# Controls_PDB.net
KiCad netlist of a schematic drawn in EAGLE
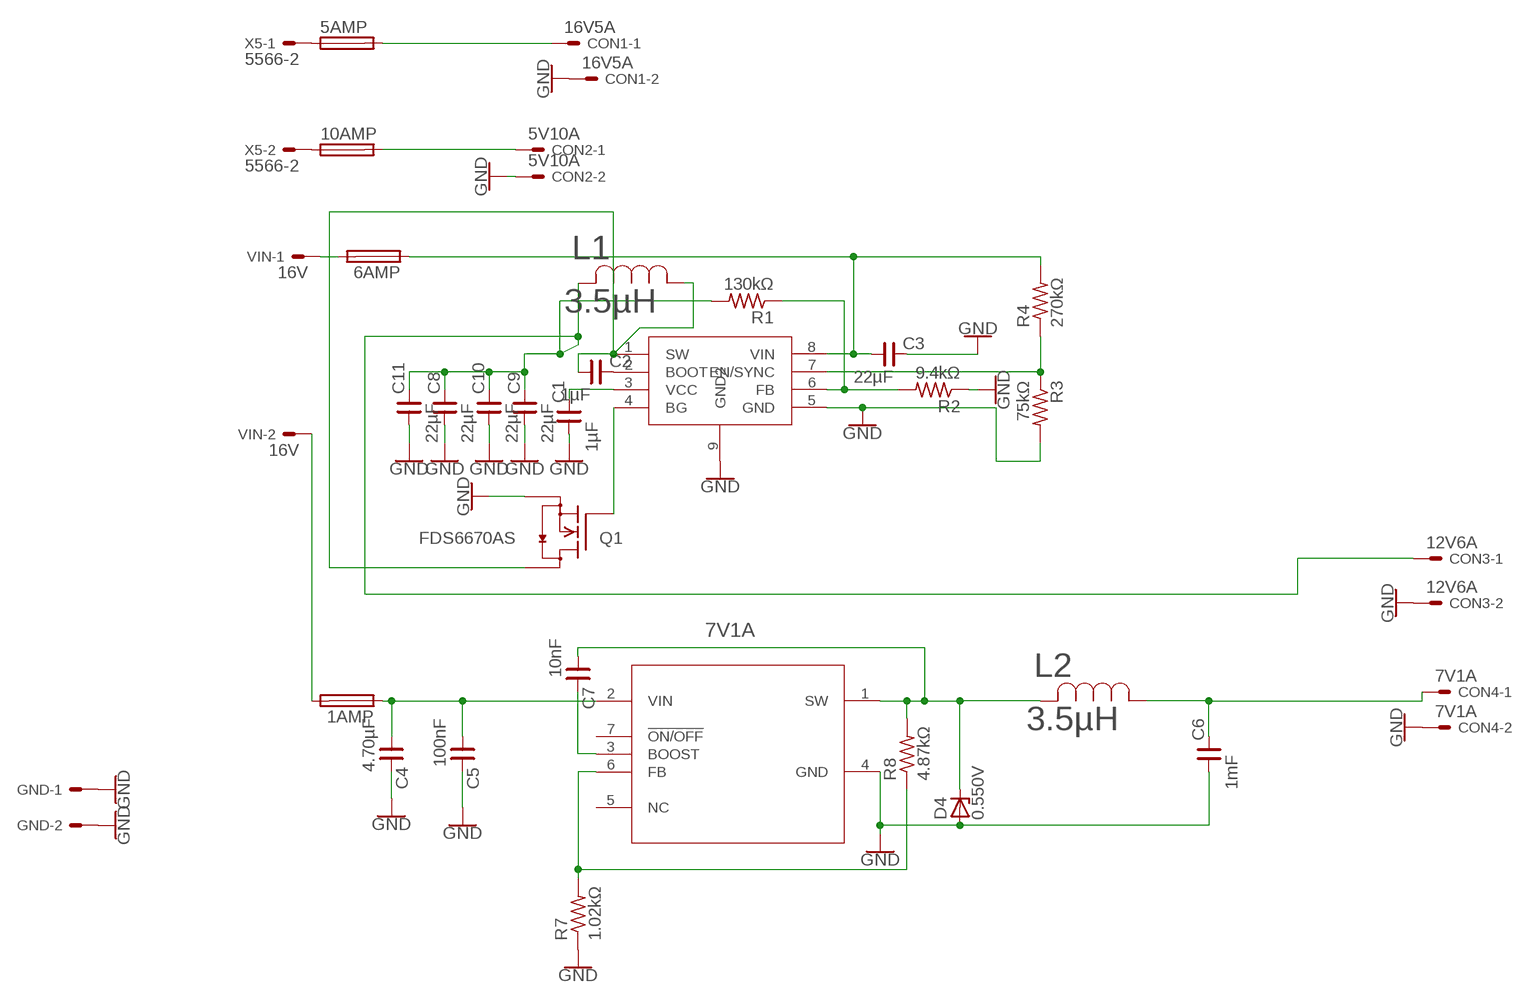
[diagram p0: schematic, sheet 1]

(export (version "E")
  (design (tool "Eeschema 10.0.6"))
  (components
    (comp (ref "1AMP")
      (value "FUSEBLANK_5X20MM")
      (footprint "eagle-import:FUSE_HOLDER_5X20MM")
      (libsource (lib "eagle-import") (part "FUSEBLANK_5X20MM"))
    )
    (comp (ref "5AMP")
      (value "FUSEBLANK_5X20MM")
      (footprint "eagle-import:FUSE_HOLDER_5X20MM")
      (libsource (lib "eagle-import") (part "FUSEBLANK_5X20MM"))
    )
    (comp (ref "6AMP")
      (value "FUSEBLANK_5X20MM")
      (footprint "eagle-import:FUSE_HOLDER_5X20MM")
      (libsource (lib "eagle-import") (part "FUSEBLANK_5X20MM"))
    )
    (comp (ref "7V1A")
      (value "LM2678T-3.3/NOPB")
      (footprint "eagle-import:TA07B")
      (fields (field (name "MANUFACTURER_PART_NUMBER") "LM2678T3.3NOPB"))
      (libsource (lib "eagle-import") (part "LM2678T-3.3/NOPB"))
    )
    (comp (ref "10AMP")
      (value "FUSEBLANK_5X20MM")
      (footprint "eagle-import:FUSE_HOLDER_5X20MM")
      (libsource (lib "eagle-import") (part "FUSEBLANK_5X20MM"))
    )
    (comp (ref "C1")
      (value "1µF")
      (footprint "eagle-import:1206")
      (libsource (lib "eagle-import") (part "CNP-1206"))
    )
    (comp (ref "C2")
      (value "1µF")
      (footprint "eagle-import:1206")
      (libsource (lib "eagle-import") (part "CNP-1206"))
    )
    (comp (ref "C3")
      (value "22µF")
      (footprint "eagle-import:1206")
      (libsource (lib "eagle-import") (part "CNP-1206"))
    )
    (comp (ref "C4")
      (value "4.70µF")
      (footprint "eagle-import:1206")
      (libsource (lib "eagle-import") (part "CNP-1206"))
    )
    (comp (ref "C5")
      (value "100nF")
      (footprint "eagle-import:1206")
      (libsource (lib "eagle-import") (part "CNP-1206"))
    )
    (comp (ref "C6")
      (value "1mF")
      (footprint "eagle-import:1206")
      (libsource (lib "eagle-import") (part "CNP-1206"))
    )
    (comp (ref "C7")
      (value "10nF")
      (footprint "eagle-import:1206")
      (libsource (lib "eagle-import") (part "CNP-1206"))
    )
    (comp (ref "C8")
      (value "22µF")
      (footprint "eagle-import:1206")
      (libsource (lib "eagle-import") (part "CNP-1206"))
    )
    (comp (ref "C9")
      (value "22µF")
      (footprint "eagle-import:1206")
      (libsource (lib "eagle-import") (part "CNP-1206"))
    )
    (comp (ref "C10")
      (value "22µF")
      (footprint "eagle-import:1206")
      (libsource (lib "eagle-import") (part "CNP-1206"))
    )
    (comp (ref "C11")
      (value "22µF")
      (footprint "eagle-import:1206")
      (libsource (lib "eagle-import") (part "CNP-1206"))
    )
    (comp (ref "CON1")
      (value "16V5A")
      (footprint "eagle-import:5566-2")
      (libsource (lib "eagle-import") (part "5566-2"))
    )
    (comp (ref "CON2")
      (value "5V10A")
      (footprint "eagle-import:5566-2")
      (libsource (lib "eagle-import") (part "5566-2"))
    )
    (comp (ref "CON3")
      (value "12V6A")
      (footprint "eagle-import:5566-2")
      (libsource (lib "eagle-import") (part "5566-2"))
    )
    (comp (ref "CON4")
      (value "7V1A")
      (footprint "eagle-import:5566-2")
      (libsource (lib "eagle-import") (part "5566-2"))
    )
    (comp (ref "D4")
      (value "0.550V")
      (footprint "eagle-import:SOD123F")
      (fields (field (name "MF") "Littelfuse") (field (name "MPN") "SMF5.0A"))
      (libsource (lib "eagle-import") (part "SMFA5.0"))
    )
    (comp (ref "GND")
      (value "5566-2")
      (footprint "eagle-import:5566-2")
      (libsource (lib "eagle-import") (part "5566-2"))
    )
    (comp (ref "L1")
      (value "3.5µH")
      (footprint "eagle-import:IND_BOURNS_SRR1260")
      (fields (field (name "MANUFACTURER_PART_NUMBER") "SRR12603R5Y"))
      (libsource (lib "eagle-import") (part "SRR1260-3R5Y"))
    )
    (comp (ref "L2")
      (value "3.5µH")
      (footprint "eagle-import:IND_BOURNS_SRR1260")
      (fields (field (name "MANUFACTURER_PART_NUMBER") "SRR12603R5Y"))
      (libsource (lib "eagle-import") (part "SRR1260-3R5Y"))
    )
    (comp (ref "Q1")
      (value "FDS6670AS")
      (footprint "eagle-import:SO-8")
      (fields (field (name "MF") "ON"))
      (libsource (lib "eagle-import") (part "FDS6670AS"))
    )
    (comp (ref "R1")
      (value "130kΩ")
      (footprint "eagle-import:R1206")
      (libsource (lib "eagle-import") (part "R-US_R1206"))
    )
    (comp (ref "R2")
      (value "9.4kΩ")
      (footprint "eagle-import:R1206")
      (libsource (lib "eagle-import") (part "R-US_R1206"))
    )
    (comp (ref "R3")
      (value "75kΩ")
      (footprint "eagle-import:R1206")
      (libsource (lib "eagle-import") (part "R-US_R1206"))
    )
    (comp (ref "R4")
      (value "270kΩ")
      (footprint "eagle-import:R1206")
      (libsource (lib "eagle-import") (part "R-US_R1206"))
    )
    (comp (ref "R7")
      (value "1.02kΩ")
      (footprint "eagle-import:R1206")
      (libsource (lib "eagle-import") (part "R-US_R1206"))
    )
    (comp (ref "R8")
      (value "4.87kΩ")
      (footprint "eagle-import:R1206")
      (libsource (lib "eagle-import") (part "R-US_R1206"))
    )
    (comp (ref "U$1")
      (value "SOIC")
      (footprint "eagle-import:SOIC127P599X175-9N")
      (libsource (lib "eagle-import") (part "SOIC"))
    )
    (comp (ref "VIN")
      (value "16V")
      (footprint "eagle-import:5566-2")
      (libsource (lib "eagle-import") (part "5566-2"))
    )
    (comp (ref "X5")
      (value "5566-2")
      (footprint "eagle-import:5566-2")
      (libsource (lib "eagle-import") (part "5566-2"))
    )
  )
  (nets
    (net (code "1") (name "GND") (class "Default")
      (node (ref "7V1A") (pin "4") (pinfunction "GND_4") (pintype "passive"))
      (node (ref "C1") (pin "P$1") (pinfunction "1_P$1") (pintype "passive"))
      (node (ref "C10") (pin "P$1") (pinfunction "1_P$1") (pintype "passive"))
      (node (ref "C11") (pin "P$1") (pinfunction "1_P$1") (pintype "passive"))
      (node (ref "C3") (pin "P$2") (pinfunction "2_P$2") (pintype "passive"))
      (node (ref "C4") (pin "P$2") (pinfunction "2_P$2") (pintype "passive"))
      (node (ref "C5") (pin "P$2") (pinfunction "2_P$2") (pintype "passive"))
      (node (ref "C6") (pin "P$1") (pinfunction "1_P$1") (pintype "passive"))
      (node (ref "C8") (pin "P$1") (pinfunction "1_P$1") (pintype "passive"))
      (node (ref "C9") (pin "P$1") (pinfunction "1_P$1") (pintype "passive"))
      (node (ref "CON1") (pin "2") (pinfunction "S_2") (pintype "passive"))
      (node (ref "CON2") (pin "2") (pinfunction "S_2") (pintype "passive"))
      (node (ref "CON3") (pin "2") (pinfunction "S_2") (pintype "passive"))
      (node (ref "CON4") (pin "2") (pinfunction "S_2") (pintype "passive"))
      (node (ref "D4") (pin "A") (pinfunction "A_A") (pintype "passive"))
      (node (ref "GND") (pin "1") (pinfunction "S_1") (pintype "passive"))
      (node (ref "GND") (pin "2") (pinfunction "S_2") (pintype "passive"))
      (node (ref "Q1") (pin "3") (pinfunction "S_3") (pintype "passive"))
      (node (ref "R2") (pin "1") (pinfunction "1_1") (pintype "passive"))
      (node (ref "R3") (pin "2") (pinfunction "2_2") (pintype "passive"))
      (node (ref "R7") (pin "1") (pinfunction "1_1") (pintype "passive"))
      (node (ref "U$1") (pin "5") (pinfunction "GND_5") (pintype "bidirectional"))
      (node (ref "U$1") (pin "9") (pinfunction "GND2_9") (pintype "bidirectional"))
    )
    (net (code "2") (name "Net-(7V1A-BOOST)") (class "Default")
      (node (ref "7V1A") (pin "3") (pinfunction "BOOST_3") (pintype "passive"))
      (node (ref "C7") (pin "P$2") (pinfunction "2_P$2") (pintype "passive"))
    )
    (net (code "3") (name "Net-(7V1A-FB)") (class "Default")
      (node (ref "7V1A") (pin "6") (pinfunction "FB_6") (pintype "passive"))
      (node (ref "R7") (pin "2") (pinfunction "2_2") (pintype "passive"))
      (node (ref "R8") (pin "1") (pinfunction "1_1") (pintype "passive"))
    )
    (net (code "4") (name "Net-(7V1A-SW)") (class "Default")
      (node (ref "7V1A") (pin "1") (pinfunction "SW_1") (pintype "output"))
      (node (ref "C7") (pin "P$1") (pinfunction "1_P$1") (pintype "passive"))
      (node (ref "D4") (pin "C") (pinfunction "C_C") (pintype "passive"))
      (node (ref "L2") (pin "2") (pinfunction "2_2") (pintype "passive"))
      (node (ref "R8") (pin "2") (pinfunction "2_2") (pintype "passive"))
    )
    (net (code "5") (name "Net-(7V1A-VIN)") (class "Default")
      (node (ref "1AMP") (pin "1") (pinfunction "1_1") (pintype "passive"))
      (node (ref "7V1A") (pin "2") (pinfunction "VIN_2") (pintype "input"))
      (node (ref "C4") (pin "P$1") (pinfunction "1_P$1") (pintype "passive"))
      (node (ref "C5") (pin "P$1") (pinfunction "1_P$1") (pintype "passive"))
    )
    (net (code "6") (name "Net-(C1-2)") (class "Default")
      (node (ref "C1") (pin "P$2") (pinfunction "2_P$2") (pintype "passive"))
      (node (ref "U$1") (pin "3") (pinfunction "VCC_3") (pintype "bidirectional"))
    )
    (net (code "7") (name "Net-(C2-1)") (class "Default")
      (node (ref "C2") (pin "P$1") (pinfunction "1_P$1") (pintype "passive"))
      (node (ref "L1") (pin "1") (pinfunction "1_1") (pintype "passive"))
      (node (ref "Q1") (pin "8") (pinfunction "D_8") (pintype "passive"))
      (node (ref "U$1") (pin "1") (pinfunction "SW_1") (pintype "bidirectional"))
    )
    (net (code "8") (name "Net-(C2-2)") (class "Default")
      (node (ref "C2") (pin "P$2") (pinfunction "2_P$2") (pintype "passive"))
      (node (ref "U$1") (pin "2") (pinfunction "BOOT_2") (pintype "bidirectional"))
    )
    (net (code "9") (name "Net-(C3-1)") (class "Default")
      (node (ref "6AMP") (pin "1") (pinfunction "1_1") (pintype "passive"))
      (node (ref "C3") (pin "P$1") (pinfunction "1_P$1") (pintype "passive"))
      (node (ref "R4") (pin "2") (pinfunction "2_2") (pintype "passive"))
      (node (ref "U$1") (pin "8") (pinfunction "VIN_8") (pintype "bidirectional"))
    )
    (net (code "10") (name "Net-(C6-2)") (class "Default")
      (node (ref "C6") (pin "P$2") (pinfunction "2_P$2") (pintype "passive"))
      (node (ref "CON4") (pin "1") (pinfunction "S_1") (pintype "passive"))
      (node (ref "L2") (pin "1") (pinfunction "1_1") (pintype "passive"))
    )
    (net (code "11") (name "Net-(C10-2)") (class "Default")
      (node (ref "C10") (pin "P$2") (pinfunction "2_P$2") (pintype "passive"))
      (node (ref "C11") (pin "P$2") (pinfunction "2_P$2") (pintype "passive"))
      (node (ref "C8") (pin "P$2") (pinfunction "2_P$2") (pintype "passive"))
      (node (ref "C9") (pin "P$2") (pinfunction "2_P$2") (pintype "passive"))
      (node (ref "CON3") (pin "1") (pinfunction "S_1") (pintype "passive"))
      (node (ref "L1") (pin "2") (pinfunction "2_2") (pintype "passive"))
      (node (ref "R1") (pin "2") (pinfunction "2_2") (pintype "passive"))
    )
    (net (code "12") (name "Net-(CON1A-S)") (class "Default")
      (node (ref "5AMP") (pin "2") (pinfunction "2_2") (pintype "passive"))
      (node (ref "CON1") (pin "1") (pinfunction "S_1") (pintype "passive"))
    )
    (net (code "13") (name "Net-(CON2A-S)") (class "Default")
      (node (ref "10AMP") (pin "2") (pinfunction "2_2") (pintype "passive"))
      (node (ref "CON2") (pin "1") (pinfunction "S_1") (pintype "passive"))
    )
    (net (code "14") (name "Net-(Q1-G)") (class "Default")
      (node (ref "Q1") (pin "4") (pinfunction "G_4") (pintype "passive"))
      (node (ref "U$1") (pin "4") (pinfunction "BG_4") (pintype "bidirectional"))
    )
    (net (code "15") (name "Net-(U$1-EN{slash}SYNC)") (class "Default")
      (node (ref "R3") (pin "1") (pinfunction "1_1") (pintype "passive"))
      (node (ref "R4") (pin "1") (pinfunction "1_1") (pintype "passive"))
      (node (ref "U$1") (pin "7") (pinfunction "EN/SYNC_7") (pintype "bidirectional"))
    )
    (net (code "16") (name "Net-(U$1-FB)") (class "Default")
      (node (ref "R1") (pin "1") (pinfunction "1_1") (pintype "passive"))
      (node (ref "R2") (pin "2") (pinfunction "2_2") (pintype "passive"))
      (node (ref "U$1") (pin "6") (pinfunction "FB_6") (pintype "bidirectional"))
    )
    (net (code "17") (name "Net-(VINA-S)") (class "Default")
      (node (ref "6AMP") (pin "2") (pinfunction "2_2") (pintype "passive"))
      (node (ref "VIN") (pin "1") (pinfunction "S_1") (pintype "passive"))
    )
    (net (code "18") (name "Net-(VINB-S)") (class "Default")
      (node (ref "1AMP") (pin "2") (pinfunction "2_2") (pintype "passive"))
      (node (ref "VIN") (pin "2") (pinfunction "S_2") (pintype "passive"))
    )
    (net (code "19") (name "Net-(X5A-S)") (class "Default")
      (node (ref "5AMP") (pin "1") (pinfunction "1_1") (pintype "passive"))
      (node (ref "X5") (pin "1") (pinfunction "S_1") (pintype "passive"))
    )
    (net (code "20") (name "Net-(X5B-S)") (class "Default")
      (node (ref "10AMP") (pin "1") (pinfunction "1_1") (pintype "passive"))
      (node (ref "X5") (pin "2") (pinfunction "S_2") (pintype "passive"))
    )
    (net (code "21") (name "unconnected-(7V1A-NC-Pad5)") (class "Default")
      (node (ref "7V1A") (pin "5") (pinfunction "NC_5") (pintype "passive"))
    )
    (net (code "22") (name "unconnected-(7V1A-~{ON{slash}OFF}-Pad7)") (class "Default")
      (node (ref "7V1A") (pin "7") (pinfunction "~{ON/OFF}_7") (pintype "passive"))
    )
    (net (code "23") (name "unconnected-(Q1-D-Pad5)") (class "Default")
      (node (ref "Q1") (pin "5") (pinfunction "D_5") (pintype "passive"))
    )
    (net (code "24") (name "unconnected-(Q1-D-Pad6)") (class "Default")
      (node (ref "Q1") (pin "6") (pinfunction "D_6") (pintype "passive"))
    )
    (net (code "25") (name "unconnected-(Q1-D-Pad7)") (class "Default")
      (node (ref "Q1") (pin "7") (pinfunction "D_7") (pintype "passive"))
    )
    (net (code "26") (name "unconnected-(Q1-S-Pad1)") (class "Default")
      (node (ref "Q1") (pin "1") (pinfunction "S_1") (pintype "passive"))
    )
    (net (code "27") (name "unconnected-(Q1-S-Pad2)") (class "Default")
      (node (ref "Q1") (pin "2") (pinfunction "S_2") (pintype "passive"))
    )
  )
)
